# Voltage_Sense.net
KiCad netlist of a schematic drawn in Altium Designer
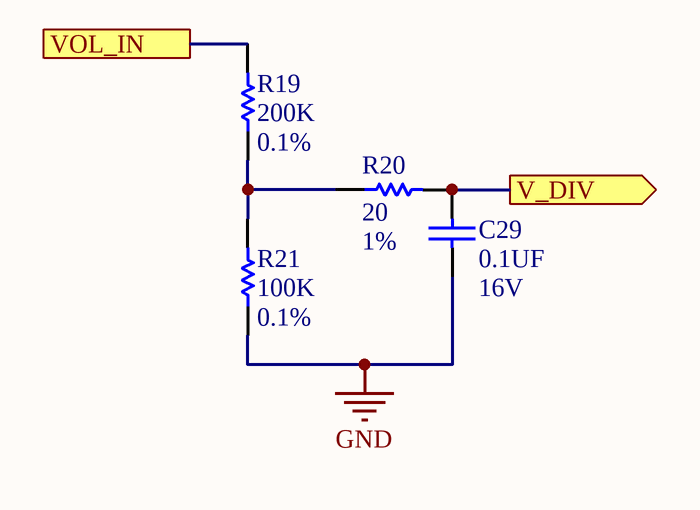
[diagram p0: Voltage Sense.SchDoc]

(export (version "E")
  (design (tool "Eeschema 10.0.6"))
  (components
    (comp (ref "C29")
      (value "CAP 0603 0.1UF 16V 10% X7R")
      (footprint "0603_CAP")
      (description "Capacitor Surface Mount 0603 Footprint 0.1UF 16V 10% Tolerance Ceramic X7R")
      (fields
        (field (name "VAL") "0.1UF")
        (field (name "VOL") "16V")
        (field (name "MANUFACTURER") "Various")
        (field (name "VOLTAGE") "16V")
      )
      (libsource (lib "Passive Components") (part "cap"))
    )
    (comp (ref "R19")
      (value "RES 0603 200K 0.1%")
      (footprint "0603_RES")
      (description "Resistor Surface Mount, 200K Ohms, 0603 Footprint, 0.1% Tolerance 0.1W")
      (fields
        (field (name "VAL") "200K")
        (field (name "TOL") "0.1%")
        (field (name "MANUFACTURER") "Various")
        (field (name "TOLERANCE") "0.1%")
      )
      (libsource (lib "Passive Components") (part "res"))
    )
    (comp (ref "R20")
      (value "RES 0603 20 1%")
      (footprint "0603_RES")
      (description "Resistor Surface Mount, 20 Ohms, 0603 Footprint, 1% Tolerance 0.1W")
      (fields
        (field (name "VAL") "20")
        (field (name "TOL") "1%")
        (field (name "MANUFACTURER") "Various")
        (field (name "TOLERANCE") "1%")
      )
      (libsource (lib "Passive Components") (part "res"))
    )
    (comp (ref "R21")
      (value "RES 0603 100K 0.1%")
      (footprint "0603_RES")
      (description "Resistor Surface Mount, 100K Ohms, 0603 Footprint, 0.1% Tolerance 0.1W")
      (fields
        (field (name "VAL") "100K")
        (field (name "TOL") "0.1%")
        (field (name "MANUFACTURER") "Various")
        (field (name "TOLERANCE") "0.1%")
      )
      (libsource (lib "Passive Components") (part "res"))
    )
  )
  (nets
    (net (code "1") (name "/VOL_IN") (class "Default")
      (node (ref "R19") (pin "2") (pinfunction "2_2") (pintype "passive"))
    )
    (net (code "2") (name "/V_DIV") (class "Default")
      (node (ref "C29") (pin "2") (pinfunction "2_2") (pintype "passive"))
      (node (ref "R20") (pin "2") (pinfunction "2_2") (pintype "passive"))
    )
    (net (code "3") (name "GND") (class "Default")
      (node (ref "C29") (pin "1") (pinfunction "1_1") (pintype "passive"))
      (node (ref "R21") (pin "1") (pinfunction "1_1") (pintype "passive"))
    )
    (net (code "4") (name "Net-(R19-Pad1)") (class "Default")
      (node (ref "R19") (pin "1") (pinfunction "1_1") (pintype "passive"))
      (node (ref "R20") (pin "1") (pinfunction "1_1") (pintype "passive"))
      (node (ref "R21") (pin "2") (pinfunction "2_2") (pintype "passive"))
    )
  )
)
